# foc.net
KiCad netlist of a schematic drawn in Altium Designer
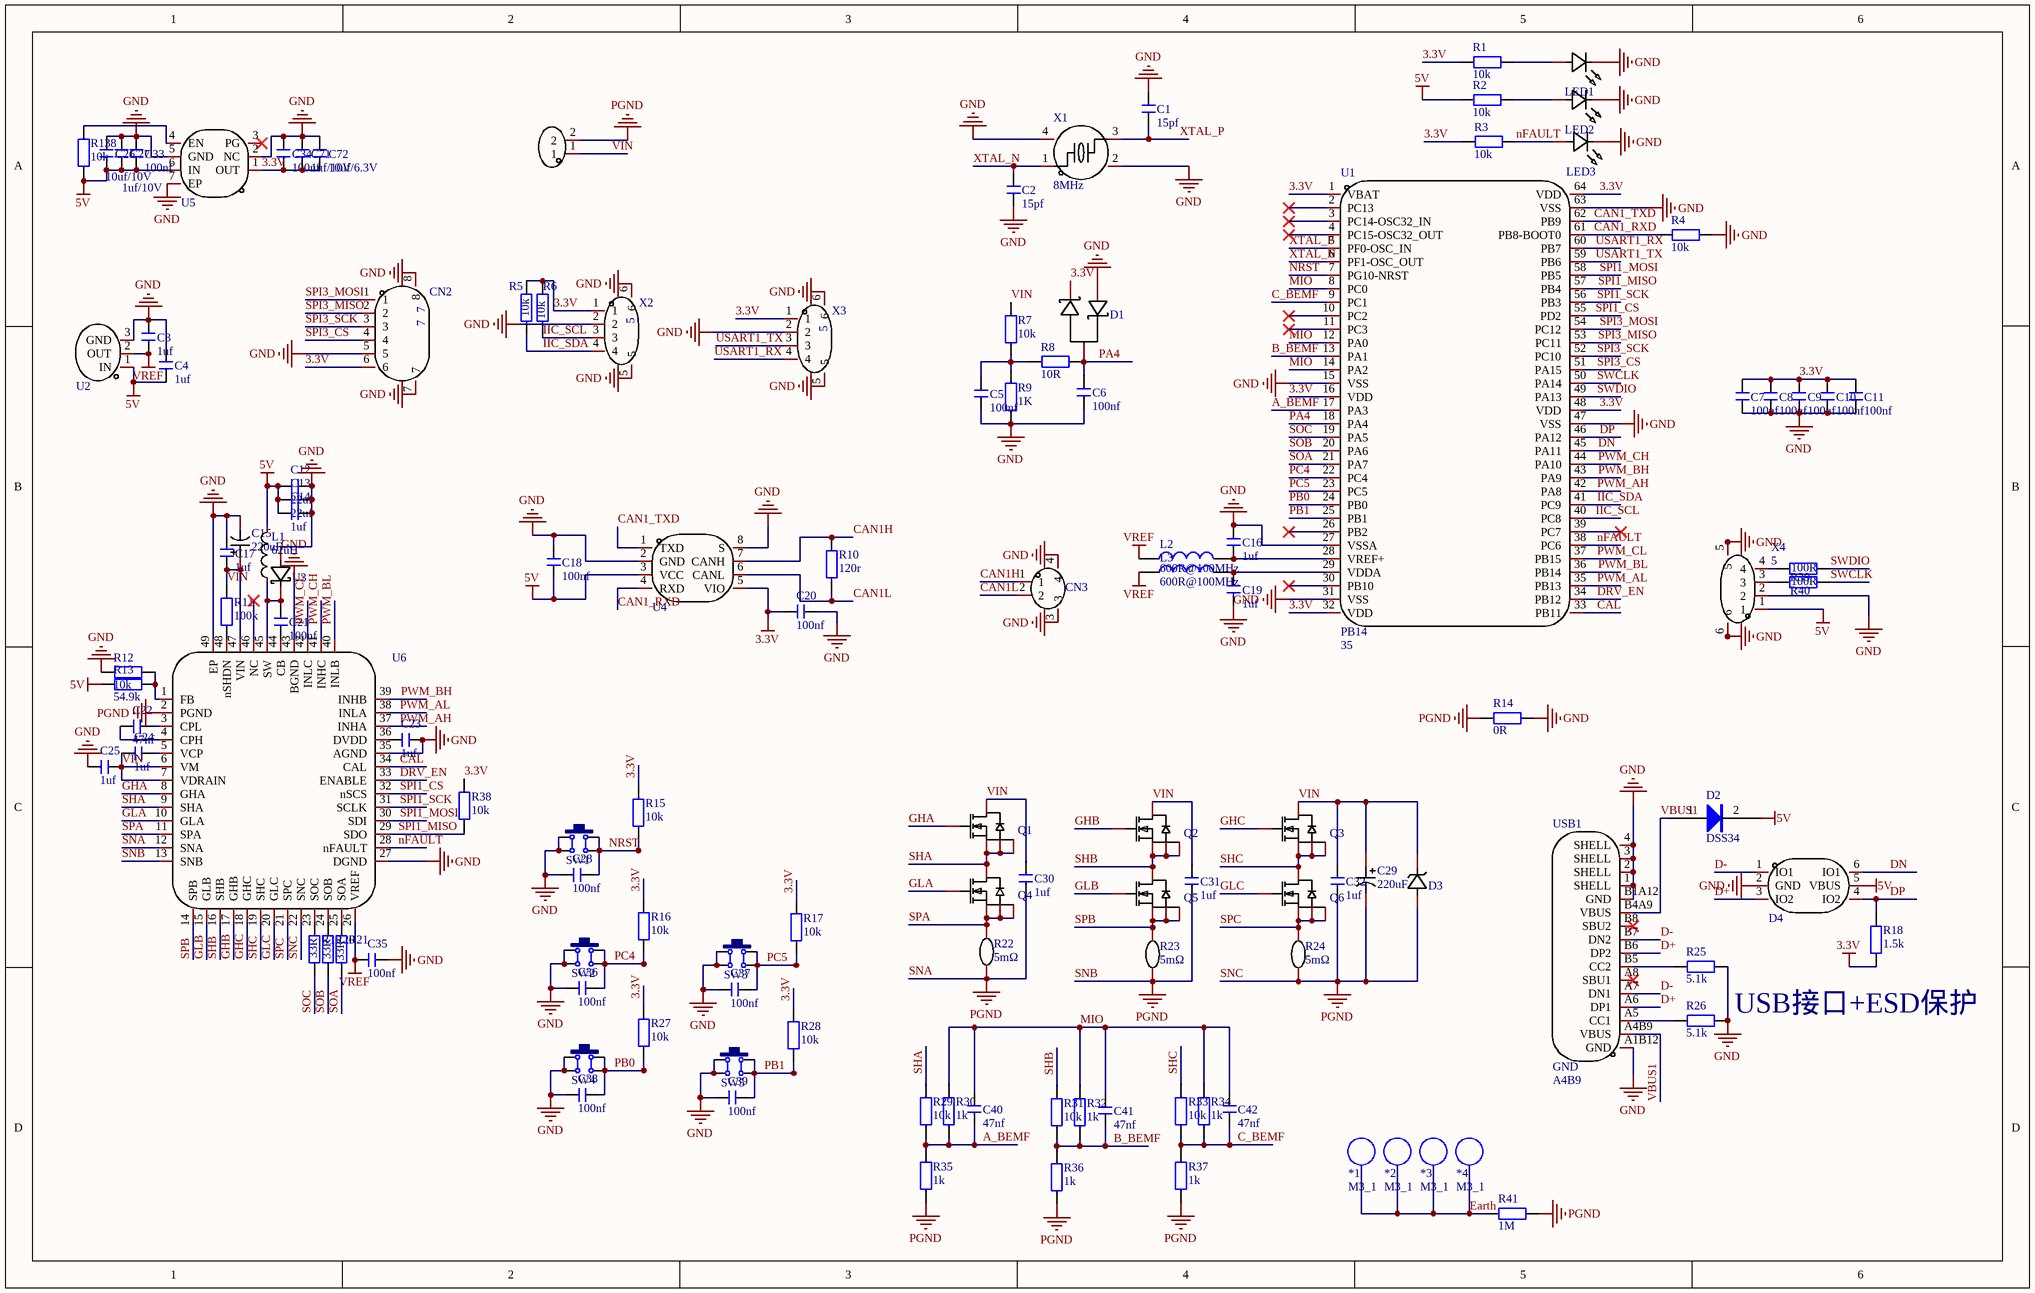
[diagram p0: foc.SchDoc]

(export (version "E")
  (design (tool "Eeschema 10.0.6"))
  (components
    (comp (ref "*1")
      (value "M3_1")
      (footprint "M3 125X250")
      (description "铜柱孔")
      (fields (field (name "版权归属") "源创客"))
      (libsource (lib "自用") (part "M3_1"))
    )
    (comp (ref "*2")
      (value "M3_1")
      (footprint "M3 125X250")
      (description "铜柱孔")
      (fields (field (name "版权归属") "源创客"))
      (libsource (lib "自用") (part "M3_1"))
    )
    (comp (ref "*3")
      (value "M3_1")
      (footprint "M3 125X250")
      (description "铜柱孔")
      (fields (field (name "版权归属") "源创客"))
      (libsource (lib "自用") (part "M3_1"))
    )
    (comp (ref "*4")
      (value "M3_1")
      (footprint "M3 125X250")
      (description "铜柱孔")
      (fields (field (name "版权归属") "源创客"))
      (libsource (lib "自用") (part "M3_1"))
    )
    (comp (ref "C1")
      (value "15pf")
      (footprint "C0402")
      (description "无极性电容")
      (fields (field (name "版权归属") "源创客"))
      (libsource (lib "自用") (part "C"))
    )
    (comp (ref "C2")
      (value "15pf")
      (footprint "C0402")
      (description "无极性电容")
      (fields (field (name "版权归属") "源创客"))
      (libsource (lib "自用") (part "C"))
    )
    (comp (ref "C3")
      (value "1uf")
      (footprint "C0402")
      (description "无极性电容")
      (fields (field (name "版权归属") "源创客"))
      (libsource (lib "自用") (part "C"))
    )
    (comp (ref "C4")
      (value "1uf")
      (footprint "C0402")
      (description "无极性电容")
      (fields (field (name "版权归属") "源创客"))
      (libsource (lib "自用") (part "C"))
    )
    (comp (ref "C5")
      (value "100nf")
      (footprint "C0402")
      (description "无极性电容")
      (fields (field (name "版权归属") "源创客"))
      (libsource (lib "自用") (part "C"))
    )
    (comp (ref "C6")
      (value "100nf")
      (footprint "C0402")
      (description "无极性电容")
      (fields (field (name "版权归属") "源创客"))
      (libsource (lib "自用") (part "C"))
    )
    (comp (ref "C7")
      (value "100nf")
      (footprint "C0402")
      (description "无极性电容")
      (fields (field (name "版权归属") "源创客"))
      (libsource (lib "自用") (part "C"))
    )
    (comp (ref "C8")
      (value "100nf")
      (footprint "C0402")
      (description "无极性电容")
      (fields (field (name "版权归属") "源创客"))
      (libsource (lib "自用") (part "C"))
    )
    (comp (ref "C9")
      (value "100nf")
      (footprint "C0402")
      (description "无极性电容")
      (fields (field (name "版权归属") "源创客"))
      (libsource (lib "自用") (part "C"))
    )
    (comp (ref "C10")
      (value "100nf")
      (footprint "C0402")
      (description "无极性电容")
      (fields (field (name "版权归属") "源创客"))
      (libsource (lib "自用") (part "C"))
    )
    (comp (ref "C11")
      (value "100nf")
      (footprint "C0402")
      (description "无极性电容")
      (fields (field (name "版权归属") "源创客"))
      (libsource (lib "自用") (part "C"))
    )
    (comp (ref "C12")
      (value "22uf")
      (footprint "C0402")
      (description "无极性电容")
      (fields (field (name "版权归属") "源创客"))
      (libsource (lib "自用") (part "C"))
    )
    (comp (ref "C13")
      (value "22uf")
      (footprint "C0402")
      (description "无极性电容")
      (fields (field (name "版权归属") "源创客"))
      (libsource (lib "自用") (part "C"))
    )
    (comp (ref "C14")
      (value "1uf")
      (footprint "C0402")
      (description "无极性电容")
      (fields (field (name "版权归属") "源创客"))
      (libsource (lib "自用") (part "C"))
    )
    (comp (ref "C15")
      (value "220uF")
      (footprint "CAP 2.5*5*11")
      (description "容值:220uF;精度:±20%;额定电压:50V;纹波电流:3.5A@100kHz;等效串联电阻(ESR):20mΩ@100kHz;类型:聚合物;")
      (fields (field (name "MANUFACTURER") "JIERR(捷而瑞)") (field (name "MANUFACTURER PART") "PA50V220M10x12"))
      (libsource (lib "自用") (part "电解电容M10*12"))
    )
    (comp (ref "C16")
      (value "1uf")
      (footprint "C0402")
      (description "无极性电容")
      (fields (field (name "版权归属") "源创客"))
      (libsource (lib "自用") (part "C"))
    )
    (comp (ref "C17")
      (value "1uf")
      (footprint "C1206")
      (description "无极性电容")
      (fields (field (name "版权归属") "源创客"))
      (libsource (lib "自用") (part "C"))
    )
    (comp (ref "C18")
      (value "100nf")
      (footprint "C0402")
      (description "无极性电容")
      (fields (field (name "版权归属") "源创客"))
      (libsource (lib "自用") (part "C"))
    )
    (comp (ref "C19")
      (value "1uf")
      (footprint "C0402")
      (description "无极性电容")
      (fields (field (name "版权归属") "源创客"))
      (libsource (lib "自用") (part "C"))
    )
    (comp (ref "C20")
      (value "100nf")
      (footprint "C0402")
      (description "无极性电容")
      (fields (field (name "版权归属") "源创客"))
      (libsource (lib "自用") (part "C"))
    )
    (comp (ref "C21")
      (value "100nf")
      (footprint "C0402")
      (description "无极性电容")
      (fields (field (name "版权归属") "源创客"))
      (libsource (lib "自用") (part "C"))
    )
    (comp (ref "C22")
      (value "47nf")
      (footprint "C0402")
      (description "无极性电容")
      (fields (field (name "版权归属") "源创客"))
      (libsource (lib "自用") (part "C"))
    )
    (comp (ref "C23")
      (value "1uf")
      (footprint "C0402")
      (description "无极性电容")
      (fields (field (name "版权归属") "源创客"))
      (libsource (lib "自用") (part "C"))
    )
    (comp (ref "C24")
      (value "1uf")
      (footprint "C0402")
      (description "无极性电容")
      (fields (field (name "版权归属") "源创客"))
      (libsource (lib "自用") (part "C"))
    )
    (comp (ref "C25")
      (value "1uf")
      (footprint "C0402")
      (description "无极性电容")
      (fields (field (name "版权归属") "源创客"))
      (libsource (lib "自用") (part "C"))
    )
    (comp (ref "C26")
      (value "10uf/10V")
      (footprint "C0603")
      (description "无极性电容")
      (fields (field (name "版权归属") "源创客"))
      (libsource (lib "自用") (part "C"))
    )
    (comp (ref "C27")
      (value "1uf/10V")
      (footprint "C0402")
      (description "无极性电容")
      (fields (field (name "版权归属") "源创客"))
      (libsource (lib "自用") (part "C"))
    )
    (comp (ref "C28")
      (value "100nf")
      (footprint "C0402")
      (description "无极性电容")
      (fields (field (name "版权归属") "源创客"))
      (libsource (lib "自用") (part "C"))
    )
    (comp (ref "C29")
      (value "220uF")
      (footprint "CAP-TH_BD10.0-P5.00-D0.6-FD_2")
      (description "容值:220uF;精度:±20%;额定电压:50V;纹波电流:3.5A@100kHz;等效串联电阻(ESR):20mΩ@100kHz;类型:聚合物;")
      (fields (field (name "MANUFACTURER") "JIERR(捷而瑞)") (field (name "MANUFACTURER PART") "PA50V220M10x12"))
      (libsource (lib "自用") (part "电解电容M10*12"))
    )
    (comp (ref "C30")
      (value "1uf")
      (footprint "C1206")
      (description "无极性电容")
      (fields (field (name "版权归属") "源创客"))
      (libsource (lib "自用") (part "C"))
    )
    (comp (ref "C31")
      (value "1uf")
      (footprint "C1206")
      (description "无极性电容")
      (fields (field (name "版权归属") "源创客"))
      (libsource (lib "自用") (part "C"))
    )
    (comp (ref "C32")
      (value "1uf")
      (footprint "C1206")
      (description "无极性电容")
      (fields (field (name "版权归属") "源创客"))
      (libsource (lib "自用") (part "C"))
    )
    (comp (ref "C33")
      (value "100nf")
      (footprint "C0402")
      (description "无极性电容")
      (fields (field (name "版权归属") "源创客"))
      (libsource (lib "自用") (part "C"))
    )
    (comp (ref "C34")
      (value "100nf")
      (footprint "C0402")
      (description "无极性电容")
      (fields (field (name "版权归属") "源创客"))
      (libsource (lib "自用") (part "C"))
    )
    (comp (ref "C35")
      (value "100nf")
      (footprint "C0402")
      (description "无极性电容")
      (fields (field (name "版权归属") "源创客"))
      (libsource (lib "自用") (part "C"))
    )
    (comp (ref "C36")
      (value "100nf")
      (footprint "C0402")
      (description "无极性电容")
      (fields (field (name "版权归属") "源创客"))
      (libsource (lib "自用") (part "C"))
    )
    (comp (ref "C37")
      (value "100nf")
      (footprint "C0402")
      (description "无极性电容")
      (fields (field (name "版权归属") "源创客"))
      (libsource (lib "自用") (part "C"))
    )
    (comp (ref "C38")
      (value "100nf")
      (footprint "C0402")
      (description "无极性电容")
      (fields (field (name "版权归属") "源创客"))
      (libsource (lib "自用") (part "C"))
    )
    (comp (ref "C39")
      (value "100nf")
      (footprint "C0402")
      (description "无极性电容")
      (fields (field (name "版权归属") "源创客"))
      (libsource (lib "自用") (part "C"))
    )
    (comp (ref "C40")
      (value "47nf")
      (footprint "C0402")
      (description "无极性电容")
      (fields (field (name "版权归属") "源创客"))
      (libsource (lib "自用") (part "C"))
    )
    (comp (ref "C41")
      (value "47nf")
      (footprint "C0402")
      (description "无极性电容")
      (fields (field (name "版权归属") "源创客"))
      (libsource (lib "自用") (part "C"))
    )
    (comp (ref "C42")
      (value "47nf")
      (footprint "C0402")
      (description "无极性电容")
      (fields (field (name "版权归属") "源创客"))
      (libsource (lib "自用") (part "C"))
    )
    (comp (ref "C71")
      (value "1uf/10V")
      (footprint "C0402")
      (description "无极性电容")
      (fields (field (name "版权归属") "源创客"))
      (libsource (lib "自用") (part "C"))
    )
    (comp (ref "C72")
      (value "10uf/6.3V")
      (footprint "C0603")
      (description "无极性电容")
      (fields (field (name "版权归属") "源创客"))
      (libsource (lib "自用") (part "C"))
    )
    (comp (ref "CN1")
      (value "XT30U-M")
      (footprint "CONN-TH_XT30U-M")
      (fields (field (name "MANUFACTURER") "AMASS(艾迈斯)"))
      (libsource (lib "自用") (part "XT30U-M"))
    )
    (comp (ref "CN2")
      (value "A1257WR-S-6P")
      (footprint "CONN-SMD_A1257WR-S-6P")
      (description "插针结构:1x6P;间距:1.25mm;安装方式:-;行距:-;总PIN数:6P;排数:1;每排PIN数:6;参考系列:GH;触头材质:黄铜;")
      (fields
        (field (name "MANUFACTURER") "CJT(长江连接器)")
        (field (name "NAME") "7")
        (field (name "NUMBER") "7")
      )
      (libsource (lib "自用") (part "GH1.25-6P"))
    )
    (comp (ref "CN3")
      (value "GH125-S02DCA-00")
      (footprint "GH1.25-2P-卧贴")
      (fields (field (name "MANUFACTURER") "JS(钜硕电子)"))
      (libsource (lib "自用") (part "GH125-2p"))
    )
    (comp (ref "D1")
      (value "LBAT54SLT1G")
      (footprint "SOT-23_L2.9-W1.3-P1.90-LS2.4-BR")
      (description "正向压降(Vf):400mV;直流反向耐压(Vr):30V;整流电流:200mA;")
      (fields (field (name "MANUFACTURER") "LRC(乐山无线电)"))
      (libsource (lib "自用") (part "LBAT54SLT1G"))
    )
    (comp (ref "D2")
      (value "DSS34")
      (footprint "SOD-123")
      (description "Diode 1N series")
      (libsource (lib "自用") (part "二极管"))
    )
    (comp (ref "D3")
      (value "SMBJ60A_C49066953")
      (footprint "SMB_L4.5-W3.7-LS5.4-RD")
      (description "极性:单向;反向截止电压(Vrwm):60V;钳位电压:96.8V;峰值脉冲电流(Ipp):6.2A;峰值脉冲功率(Ppp):600W;击穿电压:73.7V;")
      (fields (field (name "MANUFACTURER") "R+O(宏嘉诚)") (field (name "MANUFACTURER PART") "SMBJ60A"))
      (libsource (lib "自用") (part "SMBJ60A_C49066953"))
    )
    (comp (ref "D4")
      (value "USBLC6-2SC6_C2827654")
      (footprint "SOT-23-6_L2.9-W1.6-P0.95-LS2.8-BL")
      (description "极性:-;反向截止电压(Vrwm):-;最大钳位电压:-;峰值脉冲电流(Ipp)@10/1000us:-;峰值脉冲功率(Ppp)@10/1000us:-;击穿电压:-;")
      (fields
        (field (name "MANUFACTURER") "TECH PUBLIC(台舟)")
        (field (name "MANUFACTURER PART") "USBLC6-2SC6")
      )
      (libsource (lib "自用") (part "USBLC6-2SC6_C2827654"))
    )
    (comp (ref "L1")
      (value "62uH")
      (footprint "IND-SMD_L4.0-W4.0_FNR40XXS")
      (description "电感值:62uH;精度:±20%;额定电流:520mA;饱和电流(Isat):710mA;类型:磁胶屏蔽电感;")
      (fields (field (name "MANUFACTURER") "cjiang(长江微电)") (field (name "MANUFACTURER PART") "FNR4020S620MT"))
      (libsource (lib "自用") (part "FNR4020S620MT"))
    )
    (comp (ref "L2")
      (value "600R@100MHz")
      (footprint "L0603")
      (description "电感")
      (fields (field (name "版权归属") "源创客"))
      (libsource (lib "自用") (part "L_1"))
    )
    (comp (ref "L3")
      (value "600R@100MHz")
      (footprint "L0603")
      (description "电感")
      (fields (field (name "版权归属") "源创客"))
      (libsource (lib "自用") (part "L_1"))
    )
    (comp (ref "LED1")
      (value "XL-1005SURC")
      (footprint "LED0402-R-RD_RED")
      (description "发光颜色:红色;功率:55mW;正向电流:25mA;主波长:620nm;透镜颜色:无色透明透镜;色温:6000K~7000K;发光角度:120°;载带方式:正贴;工作温度:-30~+85;")
      (fields (field (name "MANUFACTURER") "XINGLIGHT(成兴光)"))
      (libsource (lib "自用") (part "LED_1"))
    )
    (comp (ref "LED2")
      (value "XL-1005SURC")
      (footprint "LED0402-R-RD_RED")
      (description "发光颜色:红色;功率:55mW;正向电流:25mA;主波长:620nm;透镜颜色:无色透明透镜;色温:6000K~7000K;发光角度:120°;载带方式:正贴;工作温度:-30~+85;")
      (fields (field (name "MANUFACTURER") "XINGLIGHT(成兴光)"))
      (libsource (lib "自用") (part "LED_1"))
    )
    (comp (ref "LED3")
      (value "XL-1005SURC")
      (footprint "LED0402-R-RD_RED")
      (description "发光颜色:红色;功率:55mW;正向电流:25mA;主波长:620nm;透镜颜色:无色透明透镜;色温:6000K~7000K;发光角度:120°;载带方式:正贴;工作温度:-30~+85;")
      (fields (field (name "MANUFACTURER") "XINGLIGHT(成兴光)"))
      (libsource (lib "自用") (part "LED_1"))
    )
    (comp (ref "Q1")
      (value "NCEP0160AG")
      (footprint "DFN-5_L4.9-W5.9-P1.27-LS6.2-BL")
      (fields (field (name "MANUFACTURER") "NCE(无锡新洁能)"))
      (libsource (lib "自用") (part "NCEP0160AG"))
    )
    (comp (ref "Q2")
      (value "NCEP0160AG")
      (footprint "DFN-5_L4.9-W5.9-P1.27-LS6.2-BL")
      (fields (field (name "MANUFACTURER") "NCE(无锡新洁能)"))
      (libsource (lib "自用") (part "NCEP0160AG"))
    )
    (comp (ref "Q3")
      (value "NCEP0160AG")
      (footprint "DFN-5_L4.9-W5.9-P1.27-LS6.2-BL")
      (fields (field (name "MANUFACTURER") "NCE(无锡新洁能)"))
      (libsource (lib "自用") (part "NCEP0160AG"))
    )
    (comp (ref "Q4")
      (value "NCEP0160AG")
      (footprint "DFN-5_L4.9-W5.9-P1.27-LS6.2-BL")
      (fields (field (name "MANUFACTURER") "NCE(无锡新洁能)"))
      (libsource (lib "自用") (part "NCEP0160AG"))
    )
    (comp (ref "Q5")
      (value "NCEP0160AG")
      (footprint "DFN-5_L4.9-W5.9-P1.27-LS6.2-BL")
      (fields (field (name "MANUFACTURER") "NCE(无锡新洁能)"))
      (libsource (lib "自用") (part "NCEP0160AG"))
    )
    (comp (ref "Q6")
      (value "NCEP0160AG")
      (footprint "DFN-5_L4.9-W5.9-P1.27-LS6.2-BL")
      (fields (field (name "MANUFACTURER") "NCE(无锡新洁能)"))
      (libsource (lib "自用") (part "NCEP0160AG"))
    )
    (comp (ref "R1")
      (value "10k")
      (footprint "R0402")
      (description "电阻")
      (fields (field (name "版权归属") "源创客"))
      (libsource (lib "自用") (part "R"))
    )
    (comp (ref "R2")
      (value "10k")
      (footprint "R0402")
      (description "电阻")
      (fields (field (name "版权归属") "源创客"))
      (libsource (lib "自用") (part "R"))
    )
    (comp (ref "R3")
      (value "10k")
      (footprint "R0402")
      (description "电阻")
      (fields (field (name "版权归属") "源创客"))
      (libsource (lib "自用") (part "R"))
    )
    (comp (ref "R4")
      (value "10k")
      (footprint "R0402")
      (description "电阻")
      (fields (field (name "版权归属") "源创客"))
      (libsource (lib "自用") (part "R"))
    )
    (comp (ref "R5")
      (value "10k")
      (footprint "R0402")
      (description "电阻")
      (fields (field (name "版权归属") "源创客"))
      (libsource (lib "自用") (part "R"))
    )
    (comp (ref "R6")
      (value "10k")
      (footprint "R0402")
      (description "电阻")
      (fields (field (name "版权归属") "源创客"))
      (libsource (lib "自用") (part "R"))
    )
    (comp (ref "R7")
      (value "10k")
      (footprint "R0402")
      (description "电阻")
      (fields (field (name "版权归属") "源创客"))
      (libsource (lib "自用") (part "R"))
    )
    (comp (ref "R8")
      (value "10R")
      (footprint "R0402")
      (description "电阻")
      (fields (field (name "版权归属") "源创客"))
      (libsource (lib "自用") (part "R"))
    )
    (comp (ref "R9")
      (value "1K")
      (footprint "R0402")
      (description "电阻")
      (fields (field (name "版权归属") "源创客"))
      (libsource (lib "自用") (part "R"))
    )
    (comp (ref "R10")
      (value "120r")
      (footprint "R0402")
      (description "电阻")
      (fields (field (name "版权归属") "源创客"))
      (libsource (lib "自用") (part "R"))
    )
    (comp (ref "R11")
      (value "100k")
      (footprint "R0402")
      (description "电阻")
      (fields (field (name "版权归属") "源创客"))
      (libsource (lib "自用") (part "R"))
    )
    (comp (ref "R12")
      (value "10k")
      (footprint "R0402")
      (description "电阻")
      (fields (field (name "版权归属") "源创客"))
      (libsource (lib "自用") (part "R"))
    )
    (comp (ref "R13")
      (value "54.9k")
      (footprint "R0402")
      (description "电阻")
      (fields (field (name "版权归属") "源创客"))
      (libsource (lib "自用") (part "R"))
    )
    (comp (ref "R14")
      (value "0R")
      (footprint "0805R")
      (description "电阻")
      (fields (field (name "版权归属") "源创客"))
      (libsource (lib "自用") (part "R"))
    )
    (comp (ref "R15")
      (value "10k")
      (footprint "R0402")
      (description "电阻")
      (fields (field (name "版权归属") "源创客"))
      (libsource (lib "自用") (part "R"))
    )
    (comp (ref "R16")
      (value "10k")
      (footprint "R0402")
      (description "电阻")
      (fields (field (name "版权归属") "源创客"))
      (libsource (lib "自用") (part "R"))
    )
    (comp (ref "R17")
      (value "10k")
      (footprint "R0402")
      (description "电阻")
      (fields (field (name "版权归属") "源创客"))
      (libsource (lib "自用") (part "R"))
    )
    (comp (ref "R18")
      (value "1.5k")
      (footprint "R0402")
      (description "电阻")
      (fields (field (name "版权归属") "源创客"))
      (libsource (lib "自用") (part "R"))
    )
    (comp (ref "R19")
      (value "33R")
      (footprint "R0402")
      (description "电阻")
      (fields (field (name "版权归属") "源创客"))
      (libsource (lib "自用") (part "R"))
    )
    (comp (ref "R20")
      (value "33R")
      (footprint "R0402")
      (description "电阻")
      (fields (field (name "版权归属") "源创客"))
      (libsource (lib "自用") (part "R"))
    )
    (comp (ref "R21")
      (value "33R")
      (footprint "R0402")
      (description "电阻")
      (fields (field (name "版权归属") "源创客"))
      (libsource (lib "自用") (part "R"))
    )
    (comp (ref "R22")
      (value "5mΩ")
      (footprint "R2512")
      (description "电阻类型:采样电阻;阻值:5mΩ;精度:±1%;功率:2W;安装方式:贴片;")
      (fields
        (field (name "MANUFACTURER") "Milliohm(毫欧)")
        (field (name "MANUFACTURER PART") "HoYLR2512-2W-5mR-1%")
      )
      (libsource (lib "自用") (part "HoYLR2512-2W-5mR-1%"))
    )
    (comp (ref "R23")
      (value "5mΩ")
      (footprint "R2512")
      (description "电阻类型:采样电阻;阻值:5mΩ;精度:±1%;功率:2W;安装方式:贴片;")
      (fields
        (field (name "MANUFACTURER") "Milliohm(毫欧)")
        (field (name "MANUFACTURER PART") "HoYLR2512-2W-5mR-1%")
      )
      (libsource (lib "自用") (part "HoYLR2512-2W-5mR-1%"))
    )
    (comp (ref "R24")
      (value "5mΩ")
      (footprint "R2512")
      (description "电阻类型:采样电阻;阻值:5mΩ;精度:±1%;功率:2W;安装方式:贴片;")
      (fields
        (field (name "MANUFACTURER") "Milliohm(毫欧)")
        (field (name "MANUFACTURER PART") "HoYLR2512-2W-5mR-1%")
      )
      (libsource (lib "自用") (part "HoYLR2512-2W-5mR-1%"))
    )
    (comp (ref "R25")
      (value "5.1k")
      (footprint "R0402")
      (description "电阻")
      (fields (field (name "版权归属") "源创客"))
      (libsource (lib "自用") (part "R"))
    )
    (comp (ref "R26")
      (value "5.1k")
      (footprint "R0402")
      (description "电阻")
      (fields (field (name "版权归属") "源创客"))
      (libsource (lib "自用") (part "R"))
    )
    (comp (ref "R27")
      (value "10k")
      (footprint "R0402")
      (description "电阻")
      (fields (field (name "版权归属") "源创客"))
      (libsource (lib "自用") (part "R"))
    )
    (comp (ref "R28")
      (value "10k")
      (footprint "R0402")
      (description "电阻")
      (fields (field (name "版权归属") "源创客"))
      (libsource (lib "自用") (part "R"))
    )
    (comp (ref "R29")
      (value "10k")
      (footprint "R0402")
      (description "电阻")
      (fields (field (name "版权归属") "源创客"))
      (libsource (lib "自用") (part "R"))
    )
    (comp (ref "R30")
      (value "1k")
      (footprint "R0402")
      (description "电阻")
      (fields (field (name "版权归属") "源创客"))
      (libsource (lib "自用") (part "R"))
    )
    (comp (ref "R31")
      (value "10k")
      (footprint "R0402")
      (description "电阻")
      (fields (field (name "版权归属") "源创客"))
      (libsource (lib "自用") (part "R"))
    )
    (comp (ref "R32")
      (value "1k")
      (footprint "R0402")
      (description "电阻")
      (fields (field (name "版权归属") "源创客"))
      (libsource (lib "自用") (part "R"))
    )
    (comp (ref "R33")
      (value "10k")
      (footprint "R0402")
      (description "电阻")
      (fields (field (name "版权归属") "源创客"))
      (libsource (lib "自用") (part "R"))
    )
    (comp (ref "R34")
      (value "1k")
      (footprint "R0402")
      (description "电阻")
      (fields (field (name "版权归属") "源创客"))
      (libsource (lib "自用") (part "R"))
    )
    (comp (ref "R35")
      (value "1k")
      (footprint "R0402")
      (description "电阻")
      (fields (field (name "版权归属") "源创客"))
      (libsource (lib "自用") (part "R"))
    )
    (comp (ref "R36")
      (value "1k")
      (footprint "R0402")
      (description "电阻")
      (fields (field (name "版权归属") "源创客"))
      (libsource (lib "自用") (part "R"))
    )
    (comp (ref "R37")
      (value "1k")
      (footprint "R0402")
      (description "电阻")
      (fields (field (name "版权归属") "源创客"))
      (libsource (lib "自用") (part "R"))
    )
    (comp (ref "R38")
      (value "10k")
      (footprint "R0402")
      (description "电阻")
      (fields (field (name "版权归属") "源创客"))
      (libsource (lib "自用") (part "R"))
    )
    (comp (ref "R39")
      (value "100R")
      (footprint "R0402")
      (description "电阻")
      (fields (field (name "版权归属") "源创客"))
      (libsource (lib "自用") (part "R"))
    )
    (comp (ref "R40")
      (value "100R")
      (footprint "R0402")
      (description "电阻")
      (fields (field (name "版权归属") "源创客"))
      (libsource (lib "自用") (part "R"))
    )
    (comp (ref "R41")
      (value "1M")
      (footprint "0805R")
      (description "电阻")
      (fields (field (name "版权归属") "源创客"))
      (libsource (lib "自用") (part "R"))
    )
    (comp (ref "R138")
      (value "10k")
      (footprint "R0402")
      (description "电阻")
      (fields (field (name "版权归属") "源创客"))
      (libsource (lib "自用") (part "R"))
    )
    (comp (ref "SW1")
      (value "smd-4*4*1.5")
      (footprint "TSW SMD-4*4*1.5")
      (description "轻触开关")
      (fields (field (name "版权归属") "源创客"))
      (libsource (lib "自用") (part "TSW DIP-6x6"))
    )
    (comp (ref "SW2")
      (value "smd-4*4*1.5")
      (footprint "TSW SMD-4*4*1.5")
      (description "轻触开关")
      (fields (field (name "版权归属") "源创客"))
      (libsource (lib "自用") (part "TSW DIP-6x6"))
    )
    (comp (ref "SW3")
      (value "smd-4*4*1.5")
      (footprint "TSW SMD-4*4*1.5")
      (description "轻触开关")
      (fields (field (name "版权归属") "源创客"))
      (libsource (lib "自用") (part "TSW DIP-6x6"))
    )
    (comp (ref "SW4")
      (value "smd-4*4*1.5")
      (footprint "TSW SMD-4*4*1.5")
      (description "轻触开关")
      (fields (field (name "版权归属") "源创客"))
      (libsource (lib "自用") (part "TSW DIP-6x6"))
    )
    (comp (ref "SW5")
      (value "smd-4*4*1.5")
      (footprint "TSW SMD-4*4*1.5")
      (description "轻触开关")
      (fields (field (name "版权归属") "源创客"))
      (libsource (lib "自用") (part "TSW DIP-6x6"))
    )
    (comp (ref "U1")
      (value "STM32G474RET6")
      (footprint "LQFP-64_L10.0-W10.0-P0.50-LS12.0-BL")
      (description "CPU内核:ARM-M4;CPU最大主频:170MHz;应用领域:-;")
      (fields
        (field (name "MANUFACTURER") "ST(意法半导体)")
        (field (name "NAME") "PB14")
        (field (name "NUMBER") "35")
      )
      (libsource (lib "自用") (part "STM32G474RET6"))
    )
    (comp (ref "U2")
      (value "REF3033AIDBZR")
      (footprint "SOT-23-3_L3.0-W1.7-P0.95-LS2.9-BR")
      (description "输出类型:固定;工作电压:3.35V~5.5V;输出电压:3.3V;输出电流:25mA;精度:±0.2%;")
      (fields (field (name "MANUFACTURER") "TI(德州仪器)") (field (name "TOLERANCE") "±0.2%"))
      (libsource (lib "自用") (part "REF3033AIDBZR"))
    )
    (comp (ref "U3")
      (value "DSK16_C22466351")
      (footprint "SOD-123FL_L2.8-W1.9-LS3.7-RD")
      (description "二极管配置:独立式;正向压降(Vf):700mV@1A;直流反向耐压(Vr):60V;整流电流:1A;")
      (fields (field (name "MANUFACTURER") "R+O(宏嘉诚)") (field (name "MANUFACTURER PART") "DSK16"))
      (libsource (lib "自用") (part "DSK16_C22466351"))
    )
    (comp (ref "U4")
      (value "TJA1051T/3")
      (footprint "SOP-8_L4.9-W3.9-P1.27-LS6.0-BL-1")
      (fields (field (name "MANUFACTURER") "Tokmas(托克马斯)"))
      (libsource (lib "自用") (part "TJA1051T/3"))
    )
    (comp (ref "U5")
      (value "LP5912-3.3DRVR")
      (footprint "WSON-6_L2.0-W2.0-P0.65-TL-EP")
      (description "输出类型:固定;最大输入电压:6.5V;输出电压:3.3V;输出电流:500mA;输出极性:正极;")
      (fields (field (name "MANUFACTURER") "TI(德州仪器)"))
      (libsource (lib "自用") (part "LP5912-3.3DRVR"))
    )
    (comp (ref "U6")
      (value "DRV8323RSRGZT")
      (footprint "VQFN-48_L7.0-W7.0-P0.50-BL-EP5.5")
      (description "DRV8323R 具有降压稳压器和电流分流放大器的最大 65V 三相智能栅极驱动器")
      (fields (field (name "MANUFACTURER") "TI(德州仪器)"))
      (libsource (lib "自用") (part "DRV8323RSRGZT"))
    )
    (comp (ref "USB1")
      (value "TYPE-C16PIN")
      (footprint "USB-C-SMD_TYPE-C16PIN")
      (description "连接器类型:Type-C;标准:-;公母:母;端口数量:1;触点数量:16P;安装方式:卧贴;额定电流 - 电源:3A;工作温度范围:-40~+85;")
      (fields
        (field (name "MANUFACTURER") "SHOU HAN(首韩)")
        (field (name "NAME") "GND")
        (field (name "NUMBER") "A4B9")
      )
      (libsource (lib "自用") (part "TYPE-C16PIN"))
    )
    (comp (ref "X1")
      (value "8MHz")
      (footprint "CRYSTAL-SMD_4P-L3.2-W2.5-BL")
      (description "频率:16MHz;负载电容:12pF;频率公差:±10ppm;")
      (fields
        (field (name "MANUFACTURER") "YXC(扬兴晶振)")
        (field (name "MANUFACTURER PART") "XL2EL89CSI-111YLC-25M")
      )
      (libsource (lib "自用") (part "XL2EL89CSI-111YLC-25M"))
    )
    (comp (ref "X2")
      (value "GH125-S04CCA-00")
      (footprint "GH1.25-4P-卧贴")
      (description "插针结构:1x4P;间距:1.25mm;安装方式:立贴;行距:-;总PIN数:4P;排数:1;每排PIN数:4;参考系列:-;额定电流:1A;工作温度范围:-25~+85;")
      (fields (field (name "MANUFACTURER") "JS(钜硕电子)") (field (name "NUMBER") "5"))
      (libsource (lib "自用") (part "GH1.25-4P_1"))
    )
    (comp (ref "X3")
      (value "GH125-S04CCA-00")
      (footprint "GH1.25-4P-卧贴")
      (description "插针结构:1x4P;间距:1.25mm;安装方式:立贴;行距:-;总PIN数:4P;排数:1;每排PIN数:4;参考系列:-;额定电流:1A;工作温度范围:-25~+85;")
      (fields (field (name "MANUFACTURER") "JS(钜硕电子)") (field (name "NUMBER") "5"))
      (libsource (lib "自用") (part "GH1.25-4P_1"))
    )
    (comp (ref "X4")
      (value "GH125-S04CCA-00")
      (footprint "GH1.25-4P-卧贴")
      (description "插针结构:1x4P;间距:1.25mm;安装方式:立贴;行距:-;总PIN数:4P;排数:1;每排PIN数:4;参考系列:-;额定电流:1A;工作温度范围:-25~+85;")
      (fields (field (name "MANUFACTURER") "JS(钜硕电子)") (field (name "NUMBER") "5"))
      (libsource (lib "自用") (part "GH1.25-4P_1"))
    )
  )
  (nets
    (net (code "1") (name "/A_BEMF") (class "Default")
      (node (ref "C40") (pin "1") (pinfunction "1_1") (pintype "passive"))
      (node (ref "R29") (pin "1") (pinfunction "1_1") (pintype "passive"))
      (node (ref "R30") (pin "1") (pinfunction "1_1") (pintype "passive"))
      (node (ref "R35") (pin "2") (pinfunction "2_2") (pintype "passive"))
      (node (ref "U1") (pin "17") (pinfunction "PA3_17") (pintype "passive"))
    )
    (net (code "2") (name "/B_BEMF") (class "Default")
      (node (ref "C41") (pin "1") (pinfunction "1_1") (pintype "passive"))
      (node (ref "R31") (pin "1") (pinfunction "1_1") (pintype "passive"))
      (node (ref "R32") (pin "1") (pinfunction "1_1") (pintype "passive"))
      (node (ref "R36") (pin "2") (pinfunction "2_2") (pintype "passive"))
      (node (ref "U1") (pin "13") (pinfunction "PA1_13") (pintype "passive"))
    )
    (net (code "3") (name "/CAL") (class "Default")
      (node (ref "U1") (pin "33") (pinfunction "PB11_33") (pintype "passive"))
      (node (ref "U6") (pin "34") (pinfunction "CAL_34") (pintype "passive"))
    )
    (net (code "4") (name "/CAN1H") (class "Default")
      (node (ref "CN3") (pin "1") (pinfunction "1_1") (pintype "passive"))
      (node (ref "R10") (pin "2") (pinfunction "2_2") (pintype "passive"))
      (node (ref "U4") (pin "7") (pinfunction "CANH_7") (pintype "passive"))
    )
    (net (code "5") (name "/CAN1L") (class "Default")
      (node (ref "CN3") (pin "2") (pinfunction "2_2") (pintype "passive"))
      (node (ref "R10") (pin "1") (pinfunction "1_1") (pintype "passive"))
      (node (ref "U4") (pin "6") (pinfunction "CANL_6") (pintype "passive"))
    )
    (net (code "6") (name "/CAN1_RXD") (class "Default")
      (node (ref "R4") (pin "2") (pinfunction "2_2") (pintype "passive"))
      (node (ref "U1") (pin "61") (pinfunction "PB8-BOOT0_61") (pintype "passive"))
      (node (ref "U4") (pin "4") (pinfunction "RXD_4") (pintype "passive"))
    )
    (net (code "7") (name "/CAN1_TXD") (class "Default")
      (node (ref "U1") (pin "62") (pinfunction "PB9_62") (pintype "passive"))
      (node (ref "U4") (pin "1") (pinfunction "TXD_1") (pintype "passive"))
    )
    (net (code "8") (name "/C_BEMF") (class "Default")
      (node (ref "C42") (pin "1") (pinfunction "1_1") (pintype "passive"))
      (node (ref "R33") (pin "1") (pinfunction "1_1") (pintype "passive"))
      (node (ref "R34") (pin "1") (pinfunction "1_1") (pintype "passive"))
      (node (ref "R37") (pin "2") (pinfunction "2_2") (pintype "passive"))
      (node (ref "U1") (pin "9") (pinfunction "PC1_9") (pintype "passive"))
    )
    (net (code "9") (name "/D+") (class "Default")
      (node (ref "D4") (pin "3") (pinfunction "IO2_3") (pintype "passive"))
      (node (ref "USB1") (pin "A6") (pinfunction "DP1_A6") (pintype "passive"))
      (node (ref "USB1") (pin "B6") (pinfunction "DP2_B6") (pintype "passive"))
    )
    (net (code "10") (name "/D-") (class "Default")
      (node (ref "D4") (pin "1") (pinfunction "IO1_1") (pintype "passive"))
      (node (ref "USB1") (pin "A7") (pinfunction "DN1_A7") (pintype "passive"))
      (node (ref "USB1") (pin "B7") (pinfunction "DN2_B7") (pintype "passive"))
    )
    (net (code "11") (name "/DN") (class "Default")
      (node (ref "D4") (pin "6") (pinfunction "IO1_6") (pintype "passive"))
      (node (ref "U1") (pin "45") (pinfunction "PA11_45") (pintype "passive"))
    )
    (net (code "12") (name "/DP") (class "Default")
      (node (ref "D4") (pin "4") (pinfunction "IO2_4") (pintype "passive"))
      (node (ref "R18") (pin "1") (pinfunction "1_1") (pintype "passive"))
      (node (ref "U1") (pin "46") (pinfunction "PA12_46") (pintype "passive"))
    )
    (net (code "13") (name "/DRV_EN") (class "Default")
      (node (ref "U1") (pin "34") (pinfunction "PB12_34") (pintype "passive"))
      (node (ref "U6") (pin "33") (pinfunction "ENABLE_33") (pintype "passive"))
    )
    (net (code "14") (name "/Earth") (class "Default")
      (node (ref "*1") (pin "1") (pinfunction "1_1") (pintype "passive"))
      (node (ref "*2") (pin "1") (pinfunction "1_1") (pintype "passive"))
      (node (ref "*3") (pin "1") (pinfunction "1_1") (pintype "passive"))
      (node (ref "*4") (pin "1") (pinfunction "1_1") (pintype "passive"))
      (node (ref "R41") (pin "2") (pinfunction "2_2") (pintype "passive"))
    )
    (net (code "15") (name "/GHA") (class "Default")
      (node (ref "Q1") (pin "4") (pinfunction "G_4") (pintype "passive"))
      (node (ref "U6") (pin "8") (pinfunction "GHA_8") (pintype "passive"))
    )
    (net (code "16") (name "/GHB") (class "Default")
      (node (ref "Q2") (pin "4") (pinfunction "G_4") (pintype "passive"))
      (node (ref "U6") (pin "17") (pinfunction "GHB_17") (pintype "passive"))
    )
    (net (code "17") (name "/GHC") (class "Default")
      (node (ref "Q3") (pin "4") (pinfunction "G_4") (pintype "passive"))
      (node (ref "U6") (pin "18") (pinfunction "GHC_18") (pintype "passive"))
    )
    (net (code "18") (name "/GLA") (class "Default")
      (node (ref "Q4") (pin "4") (pinfunction "G_4") (pintype "passive"))
      (node (ref "U6") (pin "10") (pinfunction "GLA_10") (pintype "passive"))
    )
    (net (code "19") (name "/GLB") (class "Default")
      (node (ref "Q5") (pin "4") (pinfunction "G_4") (pintype "passive"))
      (node (ref "U6") (pin "15") (pinfunction "GLB_15") (pintype "passive"))
    )
    (net (code "20") (name "/GLC") (class "Default")
      (node (ref "Q6") (pin "4") (pinfunction "G_4") (pintype "passive"))
      (node (ref "U6") (pin "20") (pinfunction "GLC_20") (pintype "passive"))
    )
    (net (code "21") (name "/IIC_SCL") (class "Default")
      (node (ref "R6") (pin "1") (pinfunction "1_1") (pintype "passive"))
      (node (ref "U1") (pin "40") (pinfunction "PC8_40") (pintype "passive"))
      (node (ref "X2") (pin "3") (pinfunction "3_3") (pintype "passive"))
    )
    (net (code "22") (name "/IIC_SDA") (class "Default")
      (node (ref "R5") (pin "1") (pinfunction "1_1") (pintype "passive"))
      (node (ref "U1") (pin "41") (pinfunction "PC9_41") (pintype "passive"))
      (node (ref "X2") (pin "4") (pinfunction "4_4") (pintype "passive"))
    )
    (net (code "23") (name "/MIO") (class "Default")
      (node (ref "C40") (pin "2") (pinfunction "2_2") (pintype "passive"))
      (node (ref "C41") (pin "2") (pinfunction "2_2") (pintype "passive"))
      (node (ref "C42") (pin "2") (pinfunction "2_2") (pintype "passive"))
      (node (ref "R30") (pin "2") (pinfunction "2_2") (pintype "passive"))
      (node (ref "R32") (pin "2") (pinfunction "2_2") (pintype "passive"))
      (node (ref "R34") (pin "2") (pinfunction "2_2") (pintype "passive"))
      (node (ref "U1") (pin "12") (pinfunction "PA0_12") (pintype "passive"))
      (node (ref "U1") (pin "14") (pinfunction "PA2_14") (pintype "passive"))
      (node (ref "U1") (pin "8") (pinfunction "PC0_8") (pintype "passive"))
    )
    (net (code "24") (name "/NRST") (class "Default")
      (node (ref "C28") (pin "2") (pinfunction "2_2") (pintype "passive"))
      (node (ref "R15") (pin "1") (pinfunction "1_1") (pintype "passive"))
      (node (ref "SW1") (pin "2") (pinfunction "2_2") (pintype "passive"))
      (node (ref "SW1") (pin "3") (pinfunction "3_3") (pintype "passive"))
      (node (ref "U1") (pin "7") (pinfunction "PG10-NRST_7") (pintype "passive"))
    )
    (net (code "25") (name "/PA4") (class "Default")
      (node (ref "C6") (pin "1") (pinfunction "1_1") (pintype "passive"))
      (node (ref "D1") (pin "3") (pinfunction "AK_3") (pintype "passive"))
      (node (ref "R8") (pin "1") (pinfunction "1_1") (pintype "passive"))
      (node (ref "U1") (pin "18") (pinfunction "PA4_18") (pintype "passive"))
    )
    (net (code "26") (name "/PB0") (class "Default")
      (node (ref "C38") (pin "2") (pinfunction "2_2") (pintype "passive"))
      (node (ref "R27") (pin "1") (pinfunction "1_1") (pintype "passive"))
      (node (ref "SW4") (pin "2") (pinfunction "2_2") (pintype "passive"))
      (node (ref "SW4") (pin "3") (pinfunction "3_3") (pintype "passive"))
      (node (ref "U1") (pin "24") (pinfunction "PB0_24") (pintype "passive"))
    )
    (net (code "27") (name "/PB1") (class "Default")
      (node (ref "C39") (pin "2") (pinfunction "2_2") (pintype "passive"))
      (node (ref "R28") (pin "1") (pinfunction "1_1") (pintype "passive"))
      (node (ref "SW5") (pin "2") (pinfunction "2_2") (pintype "passive"))
      (node (ref "SW5") (pin "3") (pinfunction "3_3") (pintype "passive"))
      (node (ref "U1") (pin "25") (pinfunction "PB1_25") (pintype "passive"))
    )
    (net (code "28") (name "/PC4") (class "Default")
      (node (ref "C36") (pin "2") (pinfunction "2_2") (pintype "passive"))
      (node (ref "R16") (pin "1") (pinfunction "1_1") (pintype "passive"))
      (node (ref "SW2") (pin "2") (pinfunction "2_2") (pintype "passive"))
      (node (ref "SW2") (pin "3") (pinfunction "3_3") (pintype "passive"))
      (node (ref "U1") (pin "22") (pinfunction "PC4_22") (pintype "passive"))
    )
    (net (code "29") (name "/PC5") (class "Default")
      (node (ref "C37") (pin "2") (pinfunction "2_2") (pintype "passive"))
      (node (ref "R17") (pin "1") (pinfunction "1_1") (pintype "passive"))
      (node (ref "SW3") (pin "2") (pinfunction "2_2") (pintype "passive"))
      (node (ref "SW3") (pin "3") (pinfunction "3_3") (pintype "passive"))
      (node (ref "U1") (pin "23") (pinfunction "PC5_23") (pintype "passive"))
    )
    (net (code "30") (name "/PWM_AH") (class "Default")
      (node (ref "U1") (pin "42") (pinfunction "PA8_42") (pintype "passive"))
      (node (ref "U6") (pin "37") (pinfunction "INHA_37") (pintype "passive"))
    )
    (net (code "31") (name "/PWM_AL") (class "Default")
      (node (ref "U1") (pin "35") (pinfunction "PB13_35") (pintype "passive"))
      (node (ref "U6") (pin "38") (pinfunction "INLA_38") (pintype "passive"))
    )
    (net (code "32") (name "/PWM_BH") (class "Default")
      (node (ref "U1") (pin "43") (pinfunction "PA9_43") (pintype "passive"))
      (node (ref "U6") (pin "39") (pinfunction "INHB_39") (pintype "passive"))
    )
    (net (code "33") (name "/PWM_BL") (class "Default")
      (node (ref "U1") (pin "36") (pinfunction "PB14_36") (pintype "passive"))
      (node (ref "U6") (pin "40") (pinfunction "INLB_40") (pintype "passive"))
    )
    (net (code "34") (name "/PWM_CH") (class "Default")
      (node (ref "U1") (pin "44") (pinfunction "PA10_44") (pintype "passive"))
      (node (ref "U6") (pin "41") (pinfunction "INHC_41") (pintype "passive"))
    )
    (net (code "35") (name "/PWM_CL") (class "Default")
      (node (ref "U1") (pin "37") (pinfunction "PB15_37") (pintype "passive"))
      (node (ref "U6") (pin "42") (pinfunction "INLC_42") (pintype "passive"))
    )
    (net (code "36") (name "/SHA") (class "Default")
      (node (ref "Q1") (pin "1") (pinfunction "S_1") (pintype "passive"))
      (node (ref "Q1") (pin "2") (pinfunction "S_2") (pintype "passive"))
      (node (ref "Q1") (pin "3") (pinfunction "S_3") (pintype "passive"))
      (node (ref "Q4") (pin "5") (pinfunction "D_5") (pintype "passive"))
      (node (ref "R29") (pin "2") (pinfunction "2_2") (pintype "passive"))
      (node (ref "U6") (pin "9") (pinfunction "SHA_9") (pintype "passive"))
    )
    (net (code "37") (name "/SHB") (class "Default")
      (node (ref "Q2") (pin "1") (pinfunction "S_1") (pintype "passive"))
      (node (ref "Q2") (pin "2") (pinfunction "S_2") (pintype "passive"))
      (node (ref "Q2") (pin "3") (pinfunction "S_3") (pintype "passive"))
      (node (ref "Q5") (pin "5") (pinfunction "D_5") (pintype "passive"))
      (node (ref "R31") (pin "2") (pinfunction "2_2") (pintype "passive"))
      (node (ref "U6") (pin "16") (pinfunction "SHB_16") (pintype "passive"))
    )
    (net (code "38") (name "/SHC") (class "Default")
      (node (ref "Q3") (pin "1") (pinfunction "S_1") (pintype "passive"))
      (node (ref "Q3") (pin "2") (pinfunction "S_2") (pintype "passive"))
      (node (ref "Q3") (pin "3") (pinfunction "S_3") (pintype "passive"))
      (node (ref "Q6") (pin "5") (pinfunction "D_5") (pintype "passive"))
      (node (ref "R33") (pin "2") (pinfunction "2_2") (pintype "passive"))
      (node (ref "U6") (pin "19") (pinfunction "SHC_19") (pintype "passive"))
    )
    (net (code "39") (name "/SOA") (class "Default")
      (node (ref "R21") (pin "1") (pinfunction "1_1") (pintype "passive"))
      (node (ref "U1") (pin "21") (pinfunction "PA7_21") (pintype "passive"))
    )
    (net (code "40") (name "/SOB") (class "Default")
      (node (ref "R20") (pin "1") (pinfunction "1_1") (pintype "passive"))
      (node (ref "U1") (pin "20") (pinfunction "PA6_20") (pintype "passive"))
    )
    (net (code "41") (name "/SOC") (class "Default")
      (node (ref "R19") (pin "1") (pinfunction "1_1") (pintype "passive"))
      (node (ref "U1") (pin "19") (pinfunction "PA5_19") (pintype "passive"))
    )
    (net (code "42") (name "/SPA") (class "Default")
      (node (ref "Q4") (pin "1") (pinfunction "S_1") (pintype "passive"))
      (node (ref "Q4") (pin "2") (pinfunction "S_2") (pintype "passive"))
      (node (ref "Q4") (pin "3") (pinfunction "S_3") (pintype "passive"))
      (node (ref "R22") (pin "2") (pinfunction "2_2") (pintype "passive"))
      (node (ref "U6") (pin "11") (pinfunction "SPA_11") (pintype "passive"))
    )
    (net (code "43") (name "/SPB") (class "Default")
      (node (ref "Q5") (pin "1") (pinfunction "S_1") (pintype "passive"))
      (node (ref "Q5") (pin "2") (pinfunction "S_2") (pintype "passive"))
      (node (ref "Q5") (pin "3") (pinfunction "S_3") (pintype "passive"))
      (node (ref "R23") (pin "2") (pinfunction "2_2") (pintype "passive"))
      (node (ref "U6") (pin "14") (pinfunction "SPB_14") (pintype "passive"))
    )
    (net (code "44") (name "/SPC") (class "Default")
      (node (ref "Q6") (pin "1") (pinfunction "S_1") (pintype "passive"))
      (node (ref "Q6") (pin "2") (pinfunction "S_2") (pintype "passive"))
      (node (ref "Q6") (pin "3") (pinfunction "S_3") (pintype "passive"))
      (node (ref "R24") (pin "2") (pinfunction "2_2") (pintype "passive"))
      (node (ref "U6") (pin "21") (pinfunction "SPC_21") (pintype "passive"))
    )
    (net (code "45") (name "/SPI1_CS") (class "Default")
      (node (ref "U1") (pin "55") (pinfunction "PD2_55") (pintype "passive"))
      (node (ref "U6") (pin "32") (pinfunction "nSCS_32") (pintype "passive"))
    )
    (net (code "46") (name "/SPI1_MISO") (class "Default")
      (node (ref "R38") (pin "1") (pinfunction "1_1") (pintype "passive"))
      (node (ref "U1") (pin "57") (pinfunction "PB4_57") (pintype "passive"))
      (node (ref "U6") (pin "29") (pinfunction "SDO_29") (pintype "passive"))
    )
    (net (code "47") (name "/SPI1_MOSI") (class "Default")
      (node (ref "U1") (pin "58") (pinfunction "PB5_58") (pintype "passive"))
      (node (ref "U6") (pin "30") (pinfunction "SDI_30") (pintype "passive"))
    )
    (net (code "48") (name "/SPI1_SCK") (class "Default")
      (node (ref "U1") (pin "56") (pinfunction "PB3_56") (pintype "passive"))
      (node (ref "U6") (pin "31") (pinfunction "SCLK_31") (pintype "passive"))
    )
    (net (code "49") (name "/SPI3_CS") (class "Default")
      (node (ref "CN2") (pin "4") (pinfunction "4_4") (pintype "passive"))
      (node (ref "U1") (pin "51") (pinfunction "PA15_51") (pintype "passive"))
    )
    (net (code "50") (name "/SPI3_MISO") (class "Default")
      (node (ref "CN2") (pin "2") (pinfunction "2_2") (pintype "passive"))
      (node (ref "U1") (pin "53") (pinfunction "PC11_53") (pintype "passive"))
    )
    (net (code "51") (name "/SPI3_MOSI") (class "Default")
      (node (ref "CN2") (pin "1") (pinfunction "1_1") (pintype "passive"))
      (node (ref "U1") (pin "54") (pinfunction "PC12_54") (pintype "passive"))
    )
    (net (code "52") (name "/SPI3_SCK") (class "Default")
      (node (ref "CN2") (pin "3") (pinfunction "3_3") (pintype "passive"))
      (node (ref "U1") (pin "52") (pinfunction "PC10_52") (pintype "passive"))
    )
    (net (code "53") (name "/SWCLK") (class "Default")
      (node (ref "R40") (pin "2") (pinfunction "2_2") (pintype "passive"))
      (node (ref "U1") (pin "50") (pinfunction "PA14_50") (pintype "passive"))
    )
    (net (code "54") (name "/SWDIO") (class "Default")
      (node (ref "R39") (pin "2") (pinfunction "2_2") (pintype "passive"))
      (node (ref "U1") (pin "49") (pinfunction "PA13_49") (pintype "passive"))
    )
    (net (code "55") (name "/USART1_RX") (class "Default")
      (node (ref "U1") (pin "60") (pinfunction "PB7_60") (pintype "passive"))
      (node (ref "X3") (pin "4") (pinfunction "4_4") (pintype "passive"))
    )
    (net (code "56") (name "/USART1_TX") (class "Default")
      (node (ref "U1") (pin "59") (pinfunction "PB6_59") (pintype "passive"))
      (node (ref "X3") (pin "3") (pinfunction "3_3") (pintype "passive"))
    )
    (net (code "57") (name "/VBUS1") (class "Default")
      (node (ref "D2") (pin "1") (pinfunction "1_1") (pintype "passive"))
      (node (ref "USB1") (pin "A4B9") (pinfunction "VBUS_A4B9") (pintype "passive"))
      (node (ref "USB1") (pin "B4A9") (pinfunction "VBUS_B4A9") (pintype "passive"))
    )
    (net (code "58") (name "/VIN") (class "Default")
      (node (ref "C15") (pin "1") (pinfunction "1_1") (pintype "passive"))
      (node (ref "C17") (pin "1") (pinfunction "1_1") (pintype "passive"))
      (node (ref "C24") (pin "1") (pinfunction "1_1") (pintype "passive"))
      (node (ref "C25") (pin "2") (pinfunction "2_2") (pintype "passive"))
      (node (ref "C29") (pin "1") (pinfunction "1_1") (pintype "passive"))
      (node (ref "C30") (pin "2") (pinfunction "2_2") (pintype "passive"))
      (node (ref "C31") (pin "2") (pinfunction "2_2") (pintype "passive"))
      (node (ref "C32") (pin "2") (pinfunction "2_2") (pintype "passive"))
      (node (ref "CN1") (pin "1") (pinfunction "1_1") (pintype "passive"))
      (node (ref "D3") (pin "1") (pinfunction "K_1") (pintype "passive"))
      (node (ref "Q1") (pin "5") (pinfunction "D_5") (pintype "passive"))
      (node (ref "Q2") (pin "5") (pinfunction "D_5") (pintype "passive"))
      (node (ref "Q3") (pin "5") (pinfunction "D_5") (pintype "passive"))
      (node (ref "R11") (pin "2") (pinfunction "2_2") (pintype "passive"))
      (node (ref "R7") (pin "2") (pinfunction "2_2") (pintype "passive"))
      (node (ref "U6") (pin "47") (pinfunction "VIN_47") (pintype "passive"))
      (node (ref "U6") (pin "6") (pinfunction "VM_6") (pintype "passive"))
      (node (ref "U6") (pin "7") (pinfunction "VDRAIN_7") (pintype "passive"))
    )
    (net (code "59") (name "/XTAL_N") (class "Default")
      (node (ref "C2") (pin "1") (pinfunction "1_1") (pintype "passive"))
      (node (ref "U1") (pin "6") (pinfunction "PF1-OSC_OUT_6") (pintype "passive"))
      (node (ref "X1") (pin "1") (pinfunction "1_1") (pintype "passive"))
    )
    (net (code "60") (name "/XTAL_P") (class "Default")
      (node (ref "C1") (pin "2") (pinfunction "2_2") (pintype "passive"))
      (node (ref "U1") (pin "5") (pinfunction "PF0-OSC_IN_5") (pintype "passive"))
      (node (ref "X1") (pin "3") (pinfunction "3_3") (pintype "passive"))
    )
    (net (code "61") (name "/nFAULT") (class "Default")
      (node (ref "LED3") (pin "1") (pinfunction "K_1") (pintype "passive"))
      (node (ref "R3") (pin "1") (pinfunction "1_1") (pintype "passive"))
      (node (ref "U1") (pin "38") (pinfunction "PC6_38") (pintype "passive"))
      (node (ref "U6") (pin "28") (pinfunction "nFAULT_28") (pintype "passive"))
    )
    (net (code "62") (name "3.3V") (class "Default")
      (node (ref "C10") (pin "1") (pinfunction "1_1") (pintype "passive"))
      (node (ref "C11") (pin "1") (pinfunction "1_1") (pintype "passive"))
      (node (ref "C20") (pin "2") (pinfunction "2_2") (pintype "passive"))
      (node (ref "C34") (pin "2") (pinfunction "2_2") (pintype "passive"))
      (node (ref "C7") (pin "1") (pinfunction "1_1") (pintype "passive"))
      (node (ref "C71") (pin "2") (pinfunction "2_2") (pintype "passive"))
      (node (ref "C72") (pin "2") (pinfunction "2_2") (pintype "passive"))
      (node (ref "C8") (pin "1") (pinfunction "1_1") (pintype "passive"))
      (node (ref "C9") (pin "1") (pinfunction "1_1") (pintype "passive"))
      (node (ref "CN2") (pin "6") (pinfunction "6_6") (pintype "passive"))
      (node (ref "D1") (pin "2") (pinfunction "K_2") (pintype "passive"))
      (node (ref "R1") (pin "2") (pinfunction "2_2") (pintype "passive"))
      (node (ref "R15") (pin "2") (pinfunction "2_2") (pintype "passive"))
      (node (ref "R16") (pin "2") (pinfunction "2_2") (pintype "passive"))
      (node (ref "R17") (pin "2") (pinfunction "2_2") (pintype "passive"))
      (node (ref "R18") (pin "2") (pinfunction "2_2") (pintype "passive"))
      (node (ref "R27") (pin "2") (pinfunction "2_2") (pintype "passive"))
      (node (ref "R28") (pin "2") (pinfunction "2_2") (pintype "passive"))
      (node (ref "R3") (pin "2") (pinfunction "2_2") (pintype "passive"))
      (node (ref "R38") (pin "2") (pinfunction "2_2") (pintype "passive"))
      (node (ref "R5") (pin "2") (pinfunction "2_2") (pintype "passive"))
      (node (ref "R6") (pin "2") (pinfunction "2_2") (pintype "passive"))
      (node (ref "U1") (pin "1") (pinfunction "VBAT_1") (pintype "passive"))
      (node (ref "U1") (pin "16") (pinfunction "VDD_16") (pintype "passive"))
      (node (ref "U1") (pin "32") (pinfunction "VDD_32") (pintype "passive"))
      (node (ref "U1") (pin "48") (pinfunction "VDD_48") (pintype "passive"))
      (node (ref "U1") (pin "64") (pinfunction "VDD_64") (pintype "passive"))
      (node (ref "U4") (pin "5") (pinfunction "VIO_5") (pintype "passive"))
      (node (ref "U5") (pin "1") (pinfunction "OUT_1") (pintype "passive"))
      (node (ref "X2") (pin "1") (pinfunction "1_1") (pintype "passive"))
      (node (ref "X3") (pin "1") (pinfunction "1_1") (pintype "passive"))
    )
    (net (code "63") (name "5V") (class "Default")
      (node (ref "C12") (pin "1") (pinfunction "1_1") (pintype "passive"))
      (node (ref "C13") (pin "1") (pinfunction "1_1") (pintype "passive"))
      (node (ref "C14") (pin "1") (pinfunction "1_1") (pintype "passive"))
      (node (ref "C18") (pin "2") (pinfunction "2_2") (pintype "passive"))
      (node (ref "C26") (pin "2") (pinfunction "2_2") (pintype "passive"))
      (node (ref "C27") (pin "2") (pinfunction "2_2") (pintype "passive"))
      (node (ref "C33") (pin "2") (pinfunction "2_2") (pintype "passive"))
      (node (ref "C4") (pin "1") (pinfunction "1_1") (pintype "passive"))
      (node (ref "D2") (pin "2") (pinfunction "2_2") (pintype "passive"))
      (node (ref "D4") (pin "5") (pinfunction "VBUS_5") (pintype "passive"))
      (node (ref "L1") (pin "2") (pinfunction "2_2") (pintype "passive"))
      (node (ref "R13") (pin "1") (pinfunction "1_1") (pintype "passive"))
      (node (ref "R138") (pin "1") (pinfunction "1_1") (pintype "passive"))
      (node (ref "R2") (pin "2") (pinfunction "2_2") (pintype "passive"))
      (node (ref "U2") (pin "1") (pinfunction "IN_1") (pintype "passive"))
      (node (ref "U4") (pin "3") (pinfunction "VCC_3") (pintype "passive"))
      (node (ref "U5") (pin "6") (pinfunction "IN_6") (pintype "passive"))
      (node (ref "X4") (pin "1") (pinfunction "1_1") (pintype "passive"))
    )
    (net (code "64") (name "GND") (class "Default")
      (node (ref "C1") (pin "1") (pinfunction "1_1") (pintype "passive"))
      (node (ref "C10") (pin "2") (pinfunction "2_2") (pintype "passive"))
      (node (ref "C11") (pin "2") (pinfunction "2_2") (pintype "passive"))
      (node (ref "C12") (pin "2") (pinfunction "2_2") (pintype "passive"))
      (node (ref "C13") (pin "2") (pinfunction "2_2") (pintype "passive"))
      (node (ref "C14") (pin "2") (pinfunction "2_2") (pintype "passive"))
      (node (ref "C15") (pin "2") (pinfunction "2_2") (pintype "passive"))
      (node (ref "C16") (pin "1") (pinfunction "1_1") (pintype "passive"))
      (node (ref "C17") (pin "2") (pinfunction "2_2") (pintype "passive"))
      (node (ref "C18") (pin "1") (pinfunction "1_1") (pintype "passive"))
      (node (ref "C19") (pin "2") (pinfunction "2_2") (pintype "passive"))
      (node (ref "C2") (pin "2") (pinfunction "2_2") (pintype "passive"))
      (node (ref "C20") (pin "1") (pinfunction "1_1") (pintype "passive"))
      (node (ref "C23") (pin "2") (pinfunction "2_2") (pintype "passive"))
      (node (ref "C25") (pin "1") (pinfunction "1_1") (pintype "passive"))
      (node (ref "C26") (pin "1") (pinfunction "1_1") (pintype "passive"))
      (node (ref "C27") (pin "1") (pinfunction "1_1") (pintype "passive"))
      (node (ref "C28") (pin "1") (pinfunction "1_1") (pintype "passive"))
      (node (ref "C3") (pin "2") (pinfunction "2_2") (pintype "passive"))
      (node (ref "C33") (pin "1") (pinfunction "1_1") (pintype "passive"))
      (node (ref "C34") (pin "1") (pinfunction "1_1") (pintype "passive"))
      (node (ref "C35") (pin "2") (pinfunction "2_2") (pintype "passive"))
      (node (ref "C36") (pin "1") (pinfunction "1_1") (pintype "passive"))
      (node (ref "C37") (pin "1") (pinfunction "1_1") (pintype "passive"))
      (node (ref "C38") (pin "1") (pinfunction "1_1") (pintype "passive"))
      (node (ref "C39") (pin "1") (pinfunction "1_1") (pintype "passive"))
      (node (ref "C4") (pin "2") (pinfunction "2_2") (pintype "passive"))
      (node (ref "C5") (pin "2") (pinfunction "2_2") (pintype "passive"))
      (node (ref "C6") (pin "2") (pinfunction "2_2") (pintype "passive"))
      (node (ref "C7") (pin "2") (pinfunction "2_2") (pintype "passive"))
      (node (ref "C71") (pin "1") (pinfunction "1_1") (pintype "passive"))
      (node (ref "C72") (pin "1") (pinfunction "1_1") (pintype "passive"))
      (node (ref "C8") (pin "2") (pinfunction "2_2") (pintype "passive"))
      (node (ref "C9") (pin "2") (pinfunction "2_2") (pintype "passive"))
      (node (ref "CN2") (pin "5") (pinfunction "5_5") (pintype "passive"))
      (node (ref "CN2") (pin "7") (pinfunction "7_7") (pintype "passive"))
      (node (ref "CN2") (pin "8") (pinfunction "8_8") (pintype "passive"))
      (node (ref "CN3") (pin "3") (pinfunction "3_3") (pintype "passive"))
      (node (ref "CN3") (pin "4") (pinfunction "4_4") (pintype "passive"))
      (node (ref "D1") (pin "1") (pinfunction "A_1") (pintype "passive"))
      (node (ref "D4") (pin "2") (pinfunction "GND_2") (pintype "passive"))
      (node (ref "LED1") (pin "2") (pinfunction "A_2") (pintype "passive"))
      (node (ref "LED2") (pin "2") (pinfunction "A_2") (pintype "passive"))
      (node (ref "LED3") (pin "2") (pinfunction "A_2") (pintype "passive"))
      (node (ref "R12") (pin "1") (pinfunction "1_1") (pintype "passive"))
      (node (ref "R14") (pin "2") (pinfunction "2_2") (pintype "passive"))
      (node (ref "R25") (pin "1") (pinfunction "1_1") (pintype "passive"))
      (node (ref "R26") (pin "1") (pinfunction "1_1") (pintype "passive"))
      (node (ref "R4") (pin "1") (pinfunction "1_1") (pintype "passive"))
      (node (ref "R9") (pin "1") (pinfunction "1_1") (pintype "passive"))
      (node (ref "SW1") (pin "1") (pinfunction "1_1") (pintype "passive"))
      (node (ref "SW1") (pin "4") (pinfunction "4_4") (pintype "passive"))
      (node (ref "SW2") (pin "1") (pinfunction "1_1") (pintype "passive"))
      (node (ref "SW2") (pin "4") (pinfunction "4_4") (pintype "passive"))
      (node (ref "SW3") (pin "1") (pinfunction "1_1") (pintype "passive"))
      (node (ref "SW3") (pin "4") (pinfunction "4_4") (pintype "passive"))
      (node (ref "SW4") (pin "1") (pinfunction "1_1") (pintype "passive"))
      (node (ref "SW4") (pin "4") (pinfunction "4_4") (pintype "passive"))
      (node (ref "SW5") (pin "1") (pinfunction "1_1") (pintype "passive"))
      (node (ref "SW5") (pin "4") (pinfunction "4_4") (pintype "passive"))
      (node (ref "U1") (pin "15") (pinfunction "VSS_15") (pintype "passive"))
      (node (ref "U1") (pin "27") (pinfunction "VSSA_27") (pintype "passive"))
      (node (ref "U1") (pin "31") (pinfunction "VSS_31") (pintype "passive"))
      (node (ref "U1") (pin "47") (pinfunction "VSS_47") (pintype "passive"))
      (node (ref "U1") (pin "63") (pinfunction "VSS_63") (pintype "passive"))
      (node (ref "U2") (pin "3") (pinfunction "GND_3") (pintype "passive"))
      (node (ref "U3") (pin "2") (pinfunction "A_2") (pintype "passive"))
      (node (ref "U4") (pin "2") (pinfunction "GND_2") (pintype "passive"))
      (node (ref "U4") (pin "8") (pinfunction "S_8") (pintype "passive"))
      (node (ref "U5") (pin "2") (pinfunction "NC_2") (pintype "passive"))
      (node (ref "U5") (pin "5") (pinfunction "GND_5") (pintype "passive"))
      (node (ref "U5") (pin "7") (pinfunction "EP_7") (pintype "passive"))
      (node (ref "U6") (pin "27") (pinfunction "DGND_27") (pintype "passive"))
      (node (ref "U6") (pin "35") (pinfunction "AGND_35") (pintype "passive"))
      (node (ref "U6") (pin "43") (pinfunction "BGND_43") (pintype "passive"))
      (node (ref "U6") (pin "49") (pinfunction "EP_49") (pintype "passive"))
      (node (ref "USB1") (pin "1") (pinfunction "SHELL_1") (pintype "passive"))
      (node (ref "USB1") (pin "2") (pinfunction "SHELL_2") (pintype "passive"))
      (node (ref "USB1") (pin "3") (pinfunction "SHELL_3") (pintype "passive"))
      (node (ref "USB1") (pin "4") (pinfunction "SHELL_4") (pintype "passive"))
      (node (ref "USB1") (pin "A1B12") (pinfunction "GND_A1B12") (pintype "passive"))
      (node (ref "USB1") (pin "B1A12") (pinfunction "GND_B1A12") (pintype "passive"))
      (node (ref "X1") (pin "2") (pinfunction "GND_2") (pintype "passive"))
      (node (ref "X1") (pin "4") (pinfunction "GND_4") (pintype "passive"))
      (node (ref "X2") (pin "2") (pinfunction "2_2") (pintype "passive"))
      (node (ref "X2") (pin "5") (pinfunction "5_5") (pintype "passive"))
      (node (ref "X2") (pin "6") (pinfunction "6_6") (pintype "passive"))
      (node (ref "X3") (pin "2") (pinfunction "2_2") (pintype "passive"))
      (node (ref "X3") (pin "5") (pinfunction "5_5") (pintype "passive"))
      (node (ref "X3") (pin "6") (pinfunction "6_6") (pintype "passive"))
      (node (ref "X4") (pin "2") (pinfunction "2_2") (pintype "passive"))
      (node (ref "X4") (pin "5") (pinfunction "5_5") (pintype "passive"))
      (node (ref "X4") (pin "6") (pinfunction "6_6") (pintype "passive"))
    )
    (net (code "65") (name "Net-(C5-Pad1)") (class "Default")
      (node (ref "C5") (pin "1") (pinfunction "1_1") (pintype "passive"))
      (node (ref "R7") (pin "1") (pinfunction "1_1") (pintype "passive"))
      (node (ref "R8") (pin "2") (pinfunction "2_2") (pintype "passive"))
      (node (ref "R9") (pin "2") (pinfunction "2_2") (pintype "passive"))
    )
    (net (code "66") (name "Net-(LED1-K)") (class "Default")
      (node (ref "LED1") (pin "1") (pinfunction "K_1") (pintype "passive"))
      (node (ref "R1") (pin "1") (pinfunction "1_1") (pintype "passive"))
    )
    (net (code "67") (name "Net-(LED2-K)") (class "Default")
      (node (ref "LED2") (pin "1") (pinfunction "K_1") (pintype "passive"))
      (node (ref "R2") (pin "1") (pinfunction "1_1") (pintype "passive"))
    )
    (net (code "68") (name "Net-(R39-Pad1)") (class "Default")
      (node (ref "R39") (pin "1") (pinfunction "1_1") (pintype "passive"))
      (node (ref "X4") (pin "4") (pinfunction "4_4") (pintype "passive"))
    )
    (net (code "69") (name "Net-(R40-Pad1)") (class "Default")
      (node (ref "R40") (pin "1") (pinfunction "1_1") (pintype "passive"))
      (node (ref "X4") (pin "3") (pinfunction "3_3") (pintype "passive"))
    )
    (net (code "70") (name "Net-(U1-VDDA)") (class "Default")
      (node (ref "C19") (pin "1") (pinfunction "1_1") (pintype "passive"))
      (node (ref "L3") (pin "2") (pinfunction "2_2") (pintype "passive"))
      (node (ref "U1") (pin "29") (pinfunction "VDDA_29") (pintype "passive"))
    )
    (net (code "71") (name "Net-(U1-VREF+)") (class "Default")
      (node (ref "C16") (pin "2") (pinfunction "2_2") (pintype "passive"))
      (node (ref "L2") (pin "2") (pinfunction "2_2") (pintype "passive"))
      (node (ref "U1") (pin "28") (pinfunction "VREF+_28") (pintype "passive"))
    )
    (net (code "72") (name "Net-(U3-K)") (class "Default")
      (node (ref "C21") (pin "2") (pinfunction "2_2") (pintype "passive"))
      (node (ref "L1") (pin "1") (pinfunction "1_1") (pintype "passive"))
      (node (ref "U3") (pin "1") (pinfunction "K_1") (pintype "passive"))
      (node (ref "U6") (pin "45") (pinfunction "SW_45") (pintype "passive"))
    )
    (net (code "73") (name "Net-(U5-EN)") (class "Default")
      (node (ref "R138") (pin "2") (pinfunction "2_2") (pintype "passive"))
      (node (ref "U5") (pin "4") (pinfunction "EN_4") (pintype "passive"))
    )
    (net (code "74") (name "Net-(U6-CB)") (class "Default")
      (node (ref "C21") (pin "1") (pinfunction "1_1") (pintype "passive"))
      (node (ref "U6") (pin "44") (pinfunction "CB_44") (pintype "passive"))
    )
    (net (code "75") (name "Net-(U6-CPH)") (class "Default")
      (node (ref "C22") (pin "1") (pinfunction "1_1") (pintype "passive"))
      (node (ref "U6") (pin "4") (pinfunction "CPH_4") (pintype "passive"))
    )
    (net (code "76") (name "Net-(U6-CPL)") (class "Default")
      (node (ref "C22") (pin "2") (pinfunction "2_2") (pintype "passive"))
      (node (ref "U6") (pin "3") (pinfunction "CPL_3") (pintype "passive"))
    )
    (net (code "77") (name "Net-(U6-DVDD)") (class "Default")
      (node (ref "C23") (pin "1") (pinfunction "1_1") (pintype "passive"))
      (node (ref "U6") (pin "36") (pinfunction "DVDD_36") (pintype "passive"))
    )
    (net (code "78") (name "Net-(U6-FB)") (class "Default")
      (node (ref "R12") (pin "2") (pinfunction "2_2") (pintype "passive"))
      (node (ref "R13") (pin "2") (pinfunction "2_2") (pintype "passive"))
      (node (ref "U6") (pin "1") (pinfunction "FB_1") (pintype "passive"))
    )
    (net (code "79") (name "Net-(U6-SOA)") (class "Default")
      (node (ref "R21") (pin "2") (pinfunction "2_2") (pintype "passive"))
      (node (ref "U6") (pin "25") (pinfunction "SOA_25") (pintype "passive"))
    )
    (net (code "80") (name "Net-(U6-SOB)") (class "Default")
      (node (ref "R20") (pin "2") (pinfunction "2_2") (pintype "passive"))
      (node (ref "U6") (pin "24") (pinfunction "SOB_24") (pintype "passive"))
    )
    (net (code "81") (name "Net-(U6-SOC)") (class "Default")
      (node (ref "R19") (pin "2") (pinfunction "2_2") (pintype "passive"))
      (node (ref "U6") (pin "23") (pinfunction "SOC_23") (pintype "passive"))
    )
    (net (code "82") (name "Net-(U6-VCP)") (class "Default")
      (node (ref "C24") (pin "2") (pinfunction "2_2") (pintype "passive"))
      (node (ref "U6") (pin "5") (pinfunction "VCP_5") (pintype "passive"))
    )
    (net (code "83") (name "Net-(U6-nSHDN)") (class "Default")
      (node (ref "R11") (pin "1") (pinfunction "1_1") (pintype "passive"))
      (node (ref "U6") (pin "48") (pinfunction "nSHDN_48") (pintype "passive"))
    )
    (net (code "84") (name "Net-(USB1-CC1)") (class "Default")
      (node (ref "R26") (pin "2") (pinfunction "2_2") (pintype "passive"))
      (node (ref "USB1") (pin "A5") (pinfunction "CC1_A5") (pintype "passive"))
    )
    (net (code "85") (name "Net-(USB1-CC2)") (class "Default")
      (node (ref "R25") (pin "2") (pinfunction "2_2") (pintype "passive"))
      (node (ref "USB1") (pin "B5") (pinfunction "CC2_B5") (pintype "passive"))
    )
    (net (code "86") (name "PGND") (class "Default")
      (node (ref "C29") (pin "2") (pinfunction "2_2") (pintype "passive"))
      (node (ref "C30") (pin "1") (pinfunction "1_1") (pintype "passive"))
      (node (ref "C31") (pin "1") (pinfunction "1_1") (pintype "passive"))
      (node (ref "C32") (pin "1") (pinfunction "1_1") (pintype "passive"))
      (node (ref "CN1") (pin "2") (pinfunction "2_2") (pintype "passive"))
      (node (ref "D3") (pin "2") (pinfunction "A_2") (pintype "passive"))
      (node (ref "R14") (pin "1") (pinfunction "1_1") (pintype "passive"))
      (node (ref "R22") (pin "1") (pinfunction "1_1") (pintype "passive"))
      (node (ref "R23") (pin "1") (pinfunction "1_1") (pintype "passive"))
      (node (ref "R24") (pin "1") (pinfunction "1_1") (pintype "passive"))
      (node (ref "R35") (pin "1") (pinfunction "1_1") (pintype "passive"))
      (node (ref "R36") (pin "1") (pinfunction "1_1") (pintype "passive"))
      (node (ref "R37") (pin "1") (pinfunction "1_1") (pintype "passive"))
      (node (ref "R41") (pin "1") (pinfunction "1_1") (pintype "passive"))
      (node (ref "U6") (pin "12") (pinfunction "SNA_12") (pintype "passive"))
      (node (ref "U6") (pin "13") (pinfunction "SNB_13") (pintype "passive"))
      (node (ref "U6") (pin "2") (pinfunction "PGND_2") (pintype "passive"))
      (node (ref "U6") (pin "22") (pinfunction "SNC_22") (pintype "passive"))
    )
    (net (code "87") (name "VREF") (class "Default")
      (node (ref "C3") (pin "1") (pinfunction "1_1") (pintype "passive"))
      (node (ref "C35") (pin "1") (pinfunction "1_1") (pintype "passive"))
      (node (ref "L2") (pin "1") (pinfunction "1_1") (pintype "passive"))
      (node (ref "L3") (pin "1") (pinfunction "1_1") (pintype "passive"))
      (node (ref "U2") (pin "2") (pinfunction "OUT_2") (pintype "passive"))
      (node (ref "U6") (pin "26") (pinfunction "VREF_26") (pintype "passive"))
    )
    (net (code "88") (name "unconnected-(U1-PB2-Pad26)") (class "Default")
      (node (ref "U1") (pin "26") (pinfunction "PB2_26") (pintype "passive+no_connect"))
    )
    (net (code "89") (name "unconnected-(U1-PB10-Pad30)") (class "Default")
      (node (ref "U1") (pin "30") (pinfunction "PB10_30") (pintype "passive+no_connect"))
    )
    (net (code "90") (name "unconnected-(U1-PC2-Pad10)") (class "Default")
      (node (ref "U1") (pin "10") (pinfunction "PC2_10") (pintype "passive+no_connect"))
    )
    (net (code "91") (name "unconnected-(U1-PC3-Pad11)") (class "Default")
      (node (ref "U1") (pin "11") (pinfunction "PC3_11") (pintype "passive+no_connect"))
    )
    (net (code "92") (name "unconnected-(U1-PC7-Pad39)") (class "Default")
      (node (ref "U1") (pin "39") (pinfunction "PC7_39") (pintype "passive+no_connect"))
    )
    (net (code "93") (name "unconnected-(U1-PC13-Pad2)") (class "Default")
      (node (ref "U1") (pin "2") (pinfunction "PC13_2") (pintype "passive+no_connect"))
    )
    (net (code "94") (name "unconnected-(U1-PC14-OSC32_IN-Pad3)") (class "Default")
      (node (ref "U1") (pin "3") (pinfunction "PC14-OSC32_IN_3") (pintype "passive+no_connect"))
    )
    (net (code "95") (name "unconnected-(U1-PC15-OSC32_OUT-Pad4)") (class "Default")
      (node (ref "U1") (pin "4") (pinfunction "PC15-OSC32_OUT_4") (pintype "passive+no_connect"))
    )
    (net (code "96") (name "unconnected-(U5-PG-Pad3)") (class "Default")
      (node (ref "U5") (pin "3") (pinfunction "PG_3") (pintype "passive+no_connect"))
    )
    (net (code "97") (name "unconnected-(U6-NC-Pad46)") (class "Default")
      (node (ref "U6") (pin "46") (pinfunction "NC_46") (pintype "passive+no_connect"))
    )
    (net (code "98") (name "unconnected-(USB1-SBU1-PadA8)") (class "Default")
      (node (ref "USB1") (pin "A8") (pinfunction "SBU1_A8") (pintype "passive+no_connect"))
    )
    (net (code "99") (name "unconnected-(USB1-SBU2-PadB8)") (class "Default")
      (node (ref "USB1") (pin "B8") (pinfunction "SBU2_B8") (pintype "passive+no_connect"))
    )
  )
)
